# 6_communication_buffers.net
KiCad netlist of a schematic drawn in Altium Designer
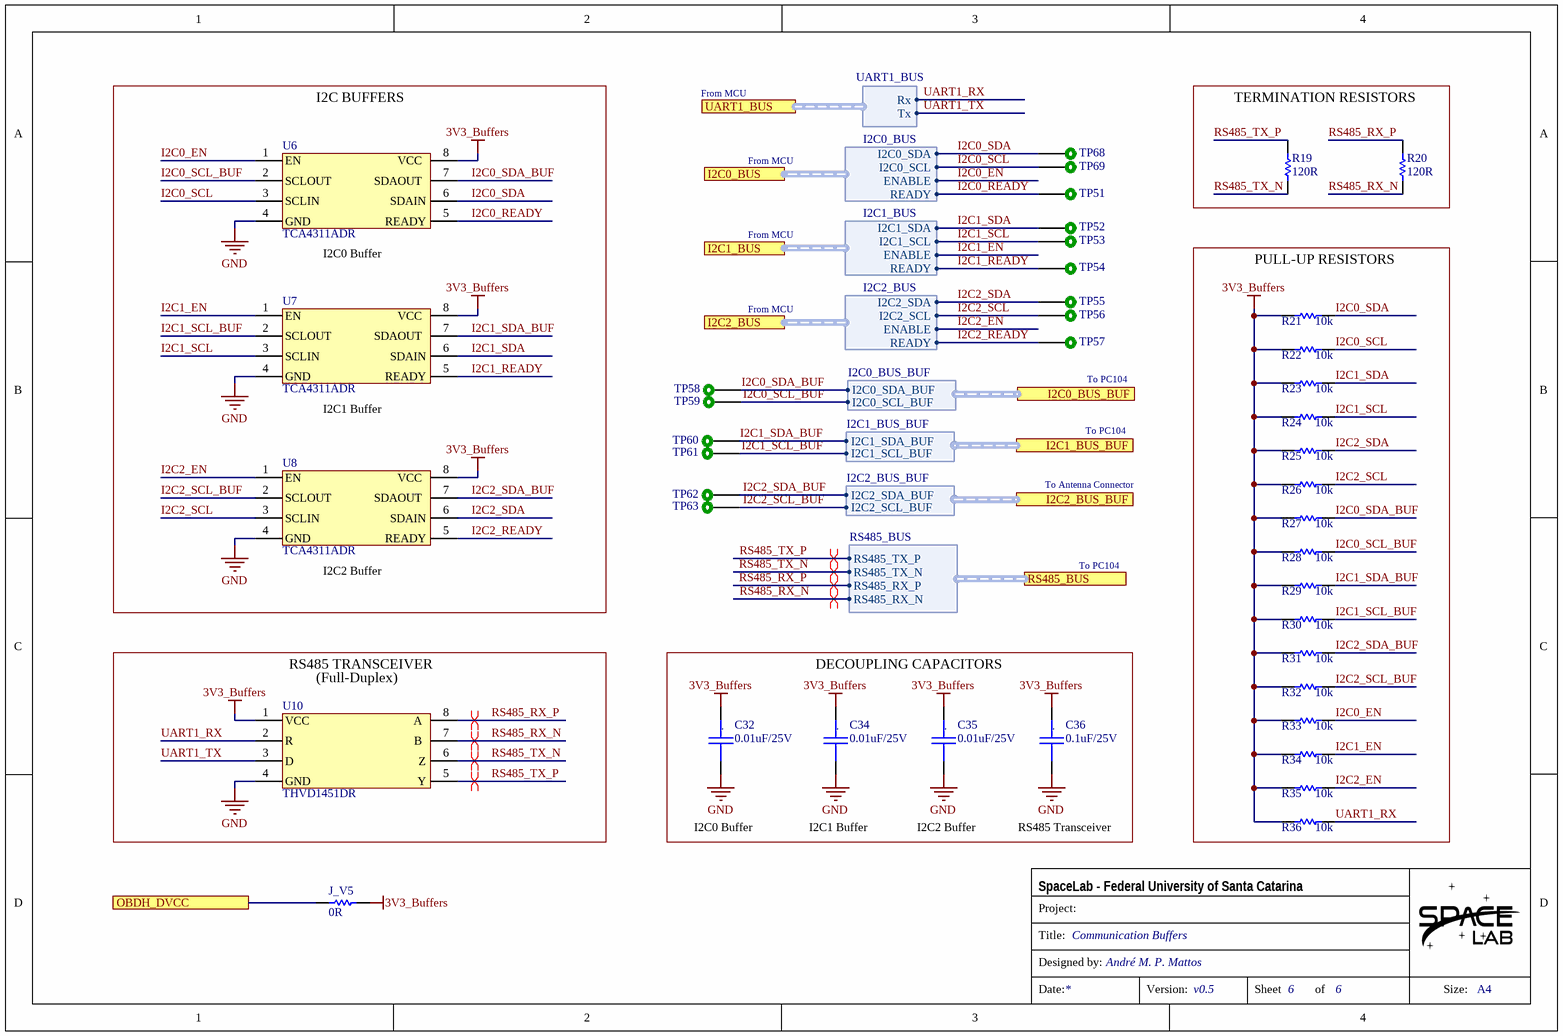
[diagram p0: 6_communication_buffers.schdoc]

(export (version "E")
  (design (tool "Eeschema 10.0.6"))
  (components
    (comp (ref "C32")
      (value "0.01uF/25V")
      (footprint "CC0805")
      (description "CAP CER 0.01uF 25V 10% X7R 0805")
      (fields (field (name "PARTNUMBER") "CL21B103KAANNNC"))
      (libsource (lib "OBDH_Eng_Model_2_ALT") (part "Cap_Cer_X7R_0.01uF_50V_0805"))
    )
    (comp (ref "C34")
      (value "0.01uF/25V")
      (footprint "CC0805")
      (description "CAP CER 0.01uF 25V 10% X7R 0805")
      (fields (field (name "PARTNUMBER") "CL21B103KAANNNC"))
      (libsource (lib "OBDH_Eng_Model_2_ALT") (part "Cap_Cer_X7R_0.01uF_50V_0805"))
    )
    (comp (ref "C35")
      (value "0.01uF/25V")
      (footprint "CC0805")
      (description "CAP CER 0.01uF 25V 10% X7R 0805")
      (fields (field (name "PARTNUMBER") "CL21B103KAANNNC"))
      (libsource (lib "OBDH_Eng_Model_2_ALT") (part "Cap_Cer_X7R_0.01uF_50V_0805"))
    )
    (comp (ref "C36")
      (value "0.1uF/25V")
      (footprint "CC0805")
      (description "CAP CER 0.1UF 25V 10% X7R 0805")
      (fields (field (name "PARTNUMBER") "CC0805KRX7R8BB104"))
      (libsource (lib "OBDH_Eng_Model_2_ALT") (part "Cap_Cer_X7R_0.1uF_25V_0805"))
    )
    (comp (ref "J_V5")
      (value "0R")
      (footprint "0805")
      (description "RES 0R OHM 1/16W JUMPER 0805")
      (fields (field (name "PARTNUMBER") "CRCW08050000Z0EA"))
      (libsource (lib "OBDH_Eng_Model_2_ALT") (part "R0R_JUMPER_1/16W_0805"))
    )
    (comp (ref "R19")
      (value "120R")
      (footprint "0805")
      (description "RES 120R OHM 1/8W 1% 0805")
      (fields (field (name "PARTNUMBER") "CRGCQ0805F120R"))
      (libsource (lib "OBDH_Eng_Model_2_ALT") (part "R120R_1%_1/4W_0805"))
    )
    (comp (ref "R20")
      (value "120R")
      (footprint "0805")
      (description "RES 120R OHM 1/8W 1% 0805")
      (fields (field (name "PARTNUMBER") "CRGCQ0805F120R"))
      (libsource (lib "OBDH_Eng_Model_2_ALT") (part "R120R_1%_1/4W_0805"))
    )
    (comp (ref "R21")
      (value "10k")
      (footprint "0805")
      (description "RES 10K OHM 1/8W 1%  0805")
      (fields (field (name "PARTNUMBER") "CRCW080510K0FKEA"))
      (libsource (lib "OBDH_Eng_Model_2_ALT") (part "R10k_1%_1/8W_0805"))
    )
    (comp (ref "R22")
      (value "10k")
      (footprint "0805")
      (description "RES 10K OHM 1/8W 1%  0805")
      (fields (field (name "PARTNUMBER") "CRCW080510K0FKEA"))
      (libsource (lib "OBDH_Eng_Model_2_ALT") (part "R10k_1%_1/8W_0805"))
    )
    (comp (ref "R23")
      (value "10k")
      (footprint "0805")
      (description "RES 10K OHM 1/8W 1%  0805")
      (fields (field (name "PARTNUMBER") "CRCW080510K0FKEA"))
      (libsource (lib "OBDH_Eng_Model_2_ALT") (part "R10k_1%_1/8W_0805"))
    )
    (comp (ref "R24")
      (value "10k")
      (footprint "0805")
      (description "RES 10K OHM 1/8W 1%  0805")
      (fields (field (name "PARTNUMBER") "CRCW080510K0FKEA"))
      (libsource (lib "OBDH_Eng_Model_2_ALT") (part "R10k_1%_1/8W_0805"))
    )
    (comp (ref "R25")
      (value "10k")
      (footprint "0805")
      (description "RES 10K OHM 1/8W 1%  0805")
      (fields (field (name "PARTNUMBER") "CRCW080510K0FKEA"))
      (libsource (lib "OBDH_Eng_Model_2_ALT") (part "R10k_1%_1/8W_0805"))
    )
    (comp (ref "R26")
      (value "10k")
      (footprint "0805")
      (description "RES 10K OHM 1/8W 1%  0805")
      (fields (field (name "PARTNUMBER") "CRCW080510K0FKEA"))
      (libsource (lib "OBDH_Eng_Model_2_ALT") (part "R10k_1%_1/8W_0805"))
    )
    (comp (ref "R27")
      (value "10k")
      (footprint "0805")
      (description "RES 10K OHM 1/8W 1%  0805")
      (fields (field (name "PARTNUMBER") "CRCW080510K0FKEA"))
      (libsource (lib "OBDH_Eng_Model_2_ALT") (part "R10k_1%_1/8W_0805"))
    )
    (comp (ref "R28")
      (value "10k")
      (footprint "0805")
      (description "RES 10K OHM 1/8W 1%  0805")
      (fields (field (name "PARTNUMBER") "CRCW080510K0FKEA"))
      (libsource (lib "OBDH_Eng_Model_2_ALT") (part "R10k_1%_1/8W_0805"))
    )
    (comp (ref "R29")
      (value "10k")
      (footprint "0805")
      (description "RES 10K OHM 1/8W 1%  0805")
      (fields (field (name "PARTNUMBER") "CRCW080510K0FKEA"))
      (libsource (lib "OBDH_Eng_Model_2_ALT") (part "R10k_1%_1/8W_0805"))
    )
    (comp (ref "R30")
      (value "10k")
      (footprint "0805")
      (description "RES 10K OHM 1/8W 1%  0805")
      (fields (field (name "PARTNUMBER") "CRCW080510K0FKEA"))
      (libsource (lib "OBDH_Eng_Model_2_ALT") (part "R10k_1%_1/8W_0805"))
    )
    (comp (ref "R31")
      (value "10k")
      (footprint "0805")
      (description "RES 10K OHM 1/8W 1%  0805")
      (fields (field (name "PARTNUMBER") "CRCW080510K0FKEA"))
      (libsource (lib "OBDH_Eng_Model_2_ALT") (part "R10k_1%_1/8W_0805"))
    )
    (comp (ref "R32")
      (value "10k")
      (footprint "0805")
      (description "RES 10K OHM 1/8W 1%  0805")
      (fields (field (name "PARTNUMBER") "CRCW080510K0FKEA"))
      (libsource (lib "OBDH_Eng_Model_2_ALT") (part "R10k_1%_1/8W_0805"))
    )
    (comp (ref "R33")
      (value "10k")
      (footprint "0805")
      (description "RES 10K OHM 1/8W 1%  0805")
      (fields (field (name "PARTNUMBER") "CRCW080510K0FKEA"))
      (libsource (lib "OBDH_Eng_Model_2_ALT") (part "R10k_1%_1/8W_0805"))
    )
    (comp (ref "R34")
      (value "10k")
      (footprint "0805")
      (description "RES 10K OHM 1/8W 1%  0805")
      (fields (field (name "PARTNUMBER") "CRCW080510K0FKEA"))
      (libsource (lib "OBDH_Eng_Model_2_ALT") (part "R10k_1%_1/8W_0805"))
    )
    (comp (ref "R35")
      (value "10k")
      (footprint "0805")
      (description "RES 10K OHM 1/8W 1%  0805")
      (fields (field (name "PARTNUMBER") "CRCW080510K0FKEA"))
      (libsource (lib "OBDH_Eng_Model_2_ALT") (part "R10k_1%_1/8W_0805"))
    )
    (comp (ref "R36")
      (value "10k")
      (footprint "0805")
      (description "RES 10K OHM 1/8W 1%  0805")
      (fields (field (name "PARTNUMBER") "CRCW080510K0FKEA"))
      (libsource (lib "OBDH_Eng_Model_2_ALT") (part "R10k_1%_1/8W_0805"))
    )
    (comp (ref "TP51")
      (value "TEST_POINT_2")
      (footprint "TEST_POINT_2")
      (description "Test point")
      (libsource (lib "OBDH_Eng_Model_2_ALT") (part "TEST_POINT_2"))
    )
    (comp (ref "TP52")
      (value "TEST_POINT_2")
      (footprint "TEST_POINT_2")
      (description "Test point")
      (libsource (lib "OBDH_Eng_Model_2_ALT") (part "TEST_POINT_2"))
    )
    (comp (ref "TP53")
      (value "TEST_POINT_2")
      (footprint "TEST_POINT_2")
      (description "Test point")
      (libsource (lib "OBDH_Eng_Model_2_ALT") (part "TEST_POINT_2"))
    )
    (comp (ref "TP54")
      (value "TEST_POINT_2")
      (footprint "TEST_POINT_2")
      (description "Test point")
      (libsource (lib "OBDH_Eng_Model_2_ALT") (part "TEST_POINT_2"))
    )
    (comp (ref "TP55")
      (value "TEST_POINT_2")
      (footprint "TEST_POINT_2")
      (description "Test point")
      (libsource (lib "OBDH_Eng_Model_2_ALT") (part "TEST_POINT_2"))
    )
    (comp (ref "TP56")
      (value "TEST_POINT_2")
      (footprint "TEST_POINT_2")
      (description "Test point")
      (libsource (lib "OBDH_Eng_Model_2_ALT") (part "TEST_POINT_2"))
    )
    (comp (ref "TP57")
      (value "TEST_POINT_2")
      (footprint "TEST_POINT_2")
      (description "Test point")
      (libsource (lib "OBDH_Eng_Model_2_ALT") (part "TEST_POINT_2"))
    )
    (comp (ref "TP58")
      (value "TEST_POINT_2")
      (footprint "TEST_POINT_2")
      (description "Test point")
      (libsource (lib "OBDH_Eng_Model_2_ALT") (part "TEST_POINT_2"))
    )
    (comp (ref "TP59")
      (value "TEST_POINT_2")
      (footprint "TEST_POINT_2")
      (description "Test point")
      (libsource (lib "OBDH_Eng_Model_2_ALT") (part "TEST_POINT_2"))
    )
    (comp (ref "TP60")
      (value "TEST_POINT_2")
      (footprint "TEST_POINT_2")
      (description "Test point")
      (libsource (lib "OBDH_Eng_Model_2_ALT") (part "TEST_POINT_2"))
    )
    (comp (ref "TP61")
      (value "TEST_POINT_2")
      (footprint "TEST_POINT_2")
      (description "Test point")
      (libsource (lib "OBDH_Eng_Model_2_ALT") (part "TEST_POINT_2"))
    )
    (comp (ref "TP62")
      (value "TEST_POINT_2")
      (footprint "TEST_POINT_2")
      (description "Test point")
      (libsource (lib "OBDH_Eng_Model_2_ALT") (part "TEST_POINT_2"))
    )
    (comp (ref "TP63")
      (value "TEST_POINT_2")
      (footprint "TEST_POINT_2")
      (description "Test point")
      (libsource (lib "OBDH_Eng_Model_2_ALT") (part "TEST_POINT_2"))
    )
    (comp (ref "TP68")
      (value "TEST_POINT_2")
      (footprint "TEST_POINT_2")
      (description "Test point")
      (libsource (lib "OBDH_Eng_Model_2_ALT") (part "TEST_POINT_2"))
    )
    (comp (ref "TP69")
      (value "TEST_POINT_2")
      (footprint "TEST_POINT_2")
      (description "Test point")
      (libsource (lib "OBDH_Eng_Model_2_ALT") (part "TEST_POINT_2"))
    )
    (comp (ref "U6")
      (value "TCA4311ADR")
      (footprint "SOIC8")
      (description "IC SIGNAL BUFFER I2C 8SOIC")
      (libsource (lib "OBDH_Eng_Model_2_ALT") (part "TCA4311ADR"))
    )
    (comp (ref "U7")
      (value "TCA4311ADR")
      (footprint "SOIC8")
      (description "IC SIGNAL BUFFER I2C 8SOIC")
      (libsource (lib "OBDH_Eng_Model_2_ALT") (part "TCA4311ADR"))
    )
    (comp (ref "U8")
      (value "TCA4311ADR")
      (footprint "SOIC8")
      (description "IC SIGNAL BUFFER I2C 8SOIC")
      (libsource (lib "OBDH_Eng_Model_2_ALT") (part "TCA4311ADR"))
    )
    (comp (ref "U10")
      (value "THVD1451DR")
      (footprint "SOIC8")
      (description "IC INTERFACE RS422_RS485 8SOIC")
      (libsource (lib "OBDH_Eng_Model_2_ALT") (part "THVD1451DR"))
    )
  )
  (nets
    (net (code "10") (name "/I2C0_EN") (class "Default")
      (node (ref "R33") (pin "1") (pinfunction "1_1") (pintype "passive"))
      (node (ref "U6") (pin "1") (pinfunction "EN_1") (pintype "passive"))
    )
    (net (code "11") (name "/I2C0_READY") (class "Default")
      (node (ref "TP51") (pin "1") (pinfunction "1_1") (pintype "passive"))
      (node (ref "U6") (pin "5") (pinfunction "READY_5") (pintype "passive"))
    )
    (net (code "12") (name "/I2C0_SCL") (class "Default")
      (node (ref "R22") (pin "1") (pinfunction "1_1") (pintype "passive"))
      (node (ref "TP69") (pin "1") (pinfunction "1_1") (pintype "passive"))
      (node (ref "U6") (pin "3") (pinfunction "SCLIN_3") (pintype "passive"))
    )
    (net (code "13") (name "/I2C0_SCL_BUF") (class "Default")
      (node (ref "R28") (pin "1") (pinfunction "1_1") (pintype "passive"))
      (node (ref "TP59") (pin "1") (pinfunction "1_1") (pintype "passive"))
      (node (ref "U6") (pin "2") (pinfunction "SCLOUT_2") (pintype "passive"))
    )
    (net (code "14") (name "/I2C0_SDA") (class "Default")
      (node (ref "R21") (pin "1") (pinfunction "1_1") (pintype "passive"))
      (node (ref "TP68") (pin "1") (pinfunction "1_1") (pintype "passive"))
      (node (ref "U6") (pin "6") (pinfunction "SDAIN_6") (pintype "passive"))
    )
    (net (code "15") (name "/I2C0_SDA_BUF") (class "Default")
      (node (ref "R27") (pin "1") (pinfunction "1_1") (pintype "passive"))
      (node (ref "TP58") (pin "1") (pinfunction "1_1") (pintype "passive"))
      (node (ref "U6") (pin "7") (pinfunction "SDAOUT_7") (pintype "passive"))
    )
    (net (code "16") (name "/I2C1_EN") (class "Default")
      (node (ref "R34") (pin "1") (pinfunction "1_1") (pintype "passive"))
      (node (ref "U7") (pin "1") (pinfunction "EN_1") (pintype "passive"))
    )
    (net (code "17") (name "/I2C1_READY") (class "Default")
      (node (ref "TP54") (pin "1") (pinfunction "1_1") (pintype "passive"))
      (node (ref "U7") (pin "5") (pinfunction "READY_5") (pintype "passive"))
    )
    (net (code "18") (name "/I2C1_SCL") (class "Default")
      (node (ref "R24") (pin "1") (pinfunction "1_1") (pintype "passive"))
      (node (ref "TP53") (pin "1") (pinfunction "1_1") (pintype "passive"))
      (node (ref "U7") (pin "3") (pinfunction "SCLIN_3") (pintype "passive"))
    )
    (net (code "19") (name "/I2C1_SCL_BUF") (class "Default")
      (node (ref "R30") (pin "1") (pinfunction "1_1") (pintype "passive"))
      (node (ref "TP61") (pin "1") (pinfunction "1_1") (pintype "passive"))
      (node (ref "U7") (pin "2") (pinfunction "SCLOUT_2") (pintype "passive"))
    )
    (net (code "20") (name "/I2C1_SDA") (class "Default")
      (node (ref "R23") (pin "1") (pinfunction "1_1") (pintype "passive"))
      (node (ref "TP52") (pin "1") (pinfunction "1_1") (pintype "passive"))
      (node (ref "U7") (pin "6") (pinfunction "SDAIN_6") (pintype "passive"))
    )
    (net (code "21") (name "/I2C1_SDA_BUF") (class "Default")
      (node (ref "R29") (pin "1") (pinfunction "1_1") (pintype "passive"))
      (node (ref "TP60") (pin "1") (pinfunction "1_1") (pintype "passive"))
      (node (ref "U7") (pin "7") (pinfunction "SDAOUT_7") (pintype "passive"))
    )
    (net (code "22") (name "/I2C2_EN") (class "Default")
      (node (ref "R35") (pin "1") (pinfunction "1_1") (pintype "passive"))
      (node (ref "U8") (pin "1") (pinfunction "EN_1") (pintype "passive"))
    )
    (net (code "23") (name "/I2C2_READY") (class "Default")
      (node (ref "TP57") (pin "1") (pinfunction "1_1") (pintype "passive"))
      (node (ref "U8") (pin "5") (pinfunction "READY_5") (pintype "passive"))
    )
    (net (code "24") (name "/I2C2_SCL") (class "Default")
      (node (ref "R26") (pin "1") (pinfunction "1_1") (pintype "passive"))
      (node (ref "TP56") (pin "1") (pinfunction "1_1") (pintype "passive"))
      (node (ref "U8") (pin "3") (pinfunction "SCLIN_3") (pintype "passive"))
    )
    (net (code "25") (name "/I2C2_SCL_BUF") (class "Default")
      (node (ref "R32") (pin "1") (pinfunction "1_1") (pintype "passive"))
      (node (ref "TP63") (pin "1") (pinfunction "1_1") (pintype "passive"))
      (node (ref "U8") (pin "2") (pinfunction "SCLOUT_2") (pintype "passive"))
    )
    (net (code "26") (name "/I2C2_SDA") (class "Default")
      (node (ref "R25") (pin "1") (pinfunction "1_1") (pintype "passive"))
      (node (ref "TP55") (pin "1") (pinfunction "1_1") (pintype "passive"))
      (node (ref "U8") (pin "6") (pinfunction "SDAIN_6") (pintype "passive"))
    )
    (net (code "27") (name "/I2C2_SDA_BUF") (class "Default")
      (node (ref "R31") (pin "1") (pinfunction "1_1") (pintype "passive"))
      (node (ref "TP62") (pin "1") (pinfunction "1_1") (pintype "passive"))
      (node (ref "U8") (pin "7") (pinfunction "SDAOUT_7") (pintype "passive"))
    )
    (net (code "28") (name "/OBDH_DVCC") (class "Default")
      (node (ref "J_V5") (pin "2") (pinfunction "2_2") (pintype "passive"))
    )
    (net (code "29") (name "/RS485_RX_N") (class "Default")
      (node (ref "R20") (pin "2") (pinfunction "2_2") (pintype "passive"))
      (node (ref "U10") (pin "7") (pinfunction "B_7") (pintype "passive"))
    )
    (net (code "30") (name "/RS485_RX_P") (class "Default")
      (node (ref "R20") (pin "1") (pinfunction "1_1") (pintype "passive"))
      (node (ref "U10") (pin "8") (pinfunction "A_8") (pintype "power_in"))
    )
    (net (code "31") (name "/RS485_TX_N") (class "Default")
      (node (ref "R19") (pin "2") (pinfunction "2_2") (pintype "passive"))
      (node (ref "U10") (pin "6") (pinfunction "Z_6") (pintype "passive"))
    )
    (net (code "32") (name "/RS485_TX_P") (class "Default")
      (node (ref "R19") (pin "1") (pinfunction "1_1") (pintype "passive"))
      (node (ref "U10") (pin "5") (pinfunction "Y_5") (pintype "passive"))
    )
    (net (code "33") (name "/UART1_RX") (class "Default")
      (node (ref "R36") (pin "1") (pinfunction "1_1") (pintype "passive"))
      (node (ref "U10") (pin "2") (pinfunction "R_2") (pintype "passive"))
    )
    (net (code "34") (name "/UART1_TX") (class "Default")
      (node (ref "U10") (pin "3") (pinfunction "D_3") (pintype "passive"))
    )
    (net (code "43") (name "3V3_Buffers") (class "Default")
      (node (ref "C32") (pin "1") (pinfunction "1_1") (pintype "passive"))
      (node (ref "C34") (pin "1") (pinfunction "1_1") (pintype "passive"))
      (node (ref "C35") (pin "1") (pinfunction "1_1") (pintype "passive"))
      (node (ref "C36") (pin "1") (pinfunction "1_1") (pintype "passive"))
      (node (ref "J_V5") (pin "1") (pinfunction "1_1") (pintype "passive"))
      (node (ref "R21") (pin "2") (pinfunction "2_2") (pintype "passive"))
      (node (ref "R22") (pin "2") (pinfunction "2_2") (pintype "passive"))
      (node (ref "R23") (pin "2") (pinfunction "2_2") (pintype "passive"))
      (node (ref "R24") (pin "2") (pinfunction "2_2") (pintype "passive"))
      (node (ref "R25") (pin "2") (pinfunction "2_2") (pintype "passive"))
      (node (ref "R26") (pin "2") (pinfunction "2_2") (pintype "passive"))
      (node (ref "R27") (pin "2") (pinfunction "2_2") (pintype "passive"))
      (node (ref "R28") (pin "2") (pinfunction "2_2") (pintype "passive"))
      (node (ref "R29") (pin "2") (pinfunction "2_2") (pintype "passive"))
      (node (ref "R30") (pin "2") (pinfunction "2_2") (pintype "passive"))
      (node (ref "R31") (pin "2") (pinfunction "2_2") (pintype "passive"))
      (node (ref "R32") (pin "2") (pinfunction "2_2") (pintype "passive"))
      (node (ref "R33") (pin "2") (pinfunction "2_2") (pintype "passive"))
      (node (ref "R34") (pin "2") (pinfunction "2_2") (pintype "passive"))
      (node (ref "R35") (pin "2") (pinfunction "2_2") (pintype "passive"))
      (node (ref "R36") (pin "2") (pinfunction "2_2") (pintype "passive"))
      (node (ref "U10") (pin "1") (pinfunction "VCC_1") (pintype "passive"))
      (node (ref "U6") (pin "8") (pinfunction "VCC_8") (pintype "power_in"))
      (node (ref "U7") (pin "8") (pinfunction "VCC_8") (pintype "power_in"))
      (node (ref "U8") (pin "8") (pinfunction "VCC_8") (pintype "power_in"))
    )
    (net (code "44") (name "GND") (class "Default")
      (node (ref "C32") (pin "2") (pinfunction "2_2") (pintype "passive"))
      (node (ref "C34") (pin "2") (pinfunction "2_2") (pintype "passive"))
      (node (ref "C35") (pin "2") (pinfunction "2_2") (pintype "passive"))
      (node (ref "C36") (pin "2") (pinfunction "2_2") (pintype "passive"))
      (node (ref "U10") (pin "4") (pinfunction "GND_4") (pintype "passive"))
      (node (ref "U6") (pin "4") (pinfunction "GND_4") (pintype "passive"))
      (node (ref "U7") (pin "4") (pinfunction "GND_4") (pintype "passive"))
      (node (ref "U8") (pin "4") (pinfunction "GND_4") (pintype "passive"))
    )
  )
)
